# Hope_Badge.net
KiCad netlist of a schematic drawn in Altium Designer
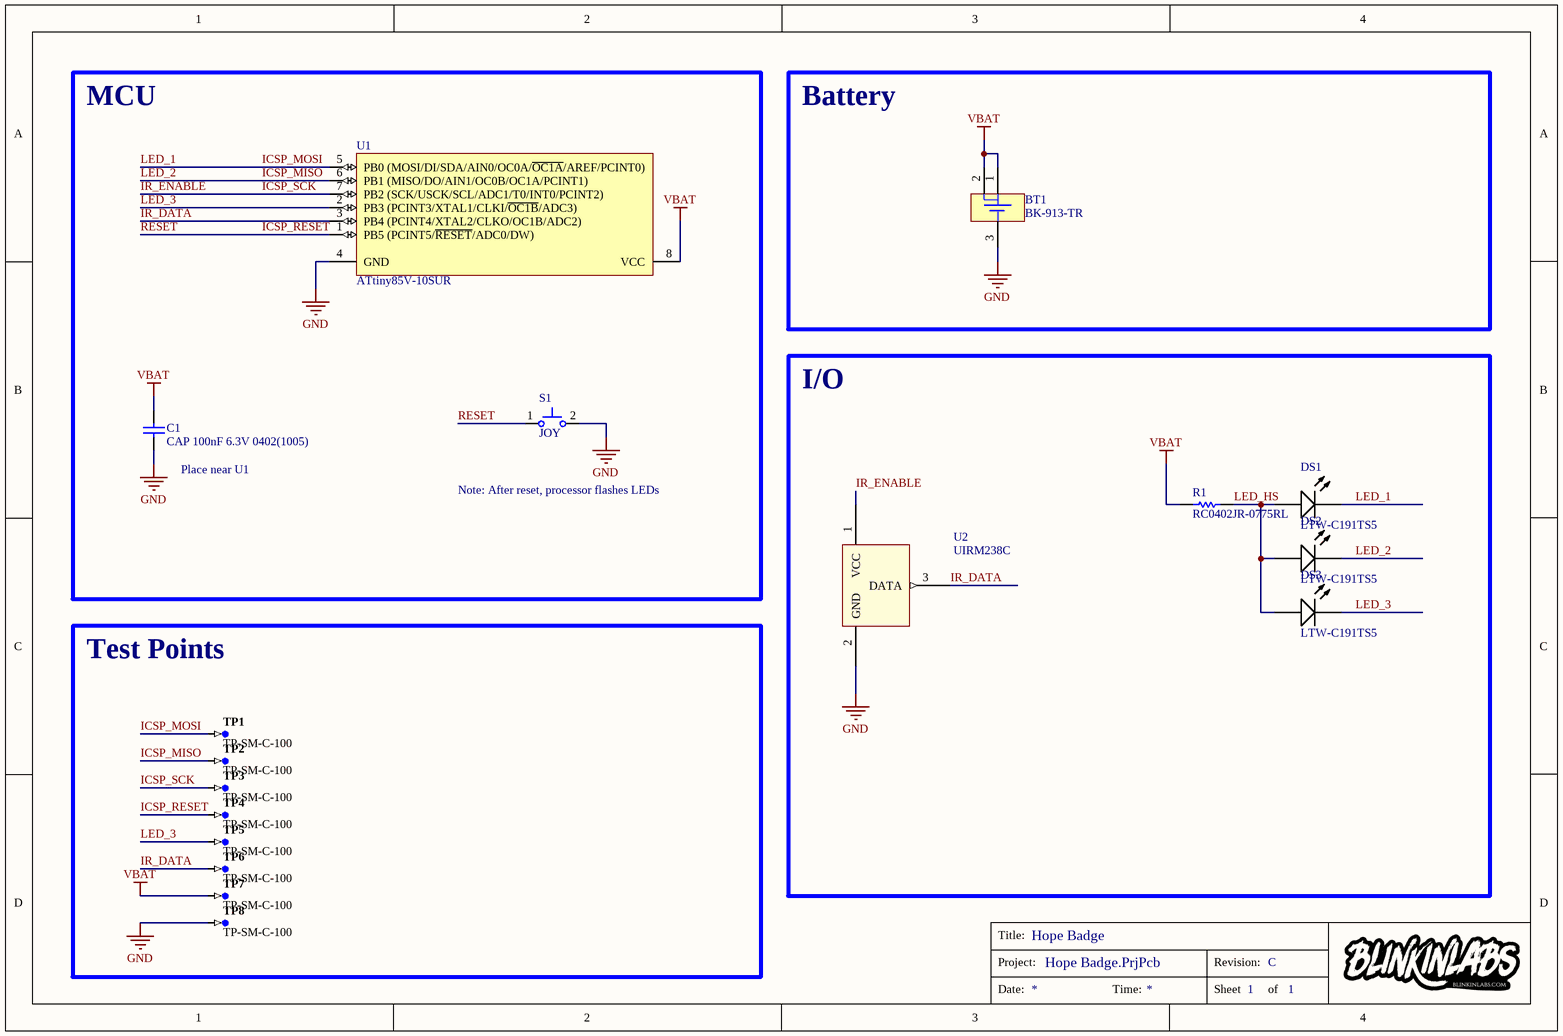
[diagram p0: Hope Badge.SchDoc]

(export (version "E")
  (design (tool "Eeschema 10.0.6"))
  (components
    (comp (ref "BT1")
      (value "BK-913-TR")
      (footprint "MPD-BK-913-3_V")
      (description "Battery Retainer for 20 mm Dia. Batteries, RoHS, Bag")
      (fields (field (name "MANUFACTURER") "Memory Protection Devices"))
      (libsource (lib "Altium Content Vault") (part "MPD-BK-913-TR-3"))
    )
    (comp (ref "C1")
      (value "CAP 100nF 6.3V 0402(1005)")
      (footprint "CAPC0402(1005)60_N")
      (description "CAP 100nF 6.3V -20% to +80% 0402 (1005 Metric) Thickness 0.6mm SMD")
      (fields (field (name "TOLERANCE") "-20% to +80%"))
      (libsource (lib "Altium Content Vault") (part "CMP-1034-02063-1"))
    )
    (comp (ref "DS1")
      (value "LTW-C191TS5")
      (footprint "LTST-LTW-C191TS5_V")
      (description "LED Uni-Color White, 70 mW, 20 mA, -20 to 80 degC, 2-Pin SMD, RoHS, Tape and Reel")
      (fields (field (name "TOLERANCE") "1%"))
      (libsource (lib "Altium Content Vault") (part "CMP-1674-00013-1"))
    )
    (comp (ref "DS2")
      (value "LTW-C191TS5")
      (footprint "LTST-LTW-C191TS5_V")
      (description "LED Uni-Color White, 70 mW, 20 mA, -20 to 80 degC, 2-Pin SMD, RoHS, Tape and Reel")
      (fields (field (name "TOLERANCE") "1%"))
      (libsource (lib "Altium Content Vault") (part "CMP-1674-00013-1"))
    )
    (comp (ref "DS3")
      (value "LTW-C191TS5")
      (footprint "LTST-LTW-C191TS5_V")
      (description "LED Uni-Color White, 70 mW, 20 mA, -20 to 80 degC, 2-Pin SMD, RoHS, Tape and Reel")
      (fields (field (name "TOLERANCE") "1%"))
      (libsource (lib "Altium Content Vault") (part "CMP-1674-00013-1"))
    )
    (comp (ref "R1")
      (value "RC0402JR-0775RL")
      (footprint "RESC1005X40X25ML5T10")
      (description "Chip Resistor, 75 Ohm, +/- 5%, 0.063 W, -55 to 155 degC, 0402 (1005 Metric), RoHS, Tape and Reel")
      (fields (field (name "TOLERANCE") "5%"))
      (libsource (lib "Altium Content Vault") (part "CMP-2002-08044-2"))
    )
    (comp (ref "S1")
      (value "JOY")
      (footprint "TS-1185")
      (description "Tact Switch, 3x4mm, no alignment pin, turtle style")
      (libsource (lib "Blinkinlabs") (part "TS-1185"))
    )
    (comp (ref "TP1")
      (value "TP-SM-C-100")
      (footprint "TP-SM-C-100")
      (description "Test Point, Surface Mount, Circular, Pad Diameter 1 mm")
      (fields (field (name "MANUFACTURER") "No Vendor"))
      (libsource (lib "Altium Content Vault") (part "TP-SM"))
    )
    (comp (ref "TP2")
      (value "TP-SM-C-100")
      (footprint "TP-SM-C-100")
      (description "Test Point, Surface Mount, Circular, Pad Diameter 1 mm")
      (fields (field (name "MANUFACTURER") "No Vendor"))
      (libsource (lib "Altium Content Vault") (part "CMP-0484-00002-2"))
    )
    (comp (ref "TP3")
      (value "TP-SM-C-100")
      (footprint "TP-SM-C-100")
      (description "Test Point, Surface Mount, Circular, Pad Diameter 1 mm")
      (fields (field (name "MANUFACTURER") "No Vendor"))
      (libsource (lib "Altium Content Vault") (part "CMP-0484-00002-2"))
    )
    (comp (ref "TP4")
      (value "TP-SM-C-100")
      (footprint "TP-SM-C-100")
      (description "Test Point, Surface Mount, Circular, Pad Diameter 1 mm")
      (fields (field (name "MANUFACTURER") "No Vendor"))
      (libsource (lib "Altium Content Vault") (part "CMP-0484-00002-2"))
    )
    (comp (ref "TP5")
      (value "TP-SM-C-100")
      (footprint "TP-SM-C-100")
      (description "Test Point, Surface Mount, Circular, Pad Diameter 1 mm")
      (fields (field (name "MANUFACTURER") "No Vendor"))
      (libsource (lib "Altium Content Vault") (part "CMP-0484-00002-2"))
    )
    (comp (ref "TP6")
      (value "TP-SM-C-100")
      (footprint "TP-SM-C-100")
      (description "Test Point, Surface Mount, Circular, Pad Diameter 1 mm")
      (fields (field (name "MANUFACTURER") "No Vendor"))
      (libsource (lib "Altium Content Vault") (part "CMP-0484-00002-2"))
    )
    (comp (ref "TP7")
      (value "TP-SM-C-100")
      (footprint "TP-SM-C-100")
      (description "Test Point, Surface Mount, Circular, Pad Diameter 1 mm")
      (fields (field (name "MANUFACTURER") "No Vendor"))
      (libsource (lib "Altium Content Vault") (part "CMP-0484-00002-2"))
    )
    (comp (ref "TP8")
      (value "TP-SM-C-100")
      (footprint "TP-SM-C-100")
      (description "Test Point, Surface Mount, Circular, Pad Diameter 1 mm")
      (fields (field (name "MANUFACTURER") "No Vendor"))
      (libsource (lib "Altium Content Vault") (part "CMP-0484-00002-2"))
    )
    (comp (ref "U1")
      (value "ATtiny85V-10SUR")
      (footprint "8S2_M")
      (libsource (lib "Altium Content Vault") (part "MC-8B-ATT25-IL8"))
    )
    (comp (ref "U2")
      (value "UIRM238C")
      (footprint "UIRM238C")
      (description "Infrared Receiver Module")
      (libsource (lib "Blinkinlabs") (part "UIRM238C"))
    )
  )
  (nets
    (net (code "1") (name "/ICSP_MISO") (class "Default")
      (node (ref "DS2") (pin "2") (pinfunction "K_2") (pintype "passive"))
      (node (ref "TP2") (pin "1") (pinfunction "1_1") (pintype "input"))
      (node (ref "U1") (pin "6") (pinfunction "PB1_(MISO/DO/AIN1/OC0B/OC1A/PCINT1)_6") (pintype "bidirectional"))
    )
    (net (code "2") (name "/ICSP_MOSI") (class "Default")
      (node (ref "DS1") (pin "2") (pinfunction "K_2") (pintype "passive"))
      (node (ref "TP1") (pin "1") (pinfunction "1_1") (pintype "input"))
      (node (ref "U1") (pin "5") (pinfunction "PB0_(MOSI/DI/SDA/AIN0/OC0A/~{OC1A}/AREF/PCINT0)_5") (pintype "bidirectional"))
    )
    (net (code "3") (name "/ICSP_RESET") (class "Default")
      (node (ref "S1") (pin "1") (pinfunction "1_1") (pintype "passive"))
      (node (ref "TP4") (pin "1") (pinfunction "1_1") (pintype "input"))
      (node (ref "U1") (pin "1") (pinfunction "PB5_(PCINT5/~{RESET}/ADC0/DW)_1") (pintype "bidirectional"))
    )
    (net (code "4") (name "/ICSP_SCK") (class "Default")
      (node (ref "TP3") (pin "1") (pinfunction "1_1") (pintype "input"))
      (node (ref "U1") (pin "7") (pinfunction "PB2_(SCK/USCK/SCL/ADC1/T0/INT0/PCINT2)_7") (pintype "bidirectional"))
      (node (ref "U2") (pin "1") (pinfunction "VCC_1") (pintype "power_in"))
    )
    (net (code "5") (name "/IR_DATA") (class "Default")
      (node (ref "TP6") (pin "1") (pinfunction "1_1") (pintype "input"))
      (node (ref "U1") (pin "3") (pinfunction "PB4_(PCINT4/XTAL2/CLKO/OC1B/ADC2)_3") (pintype "bidirectional"))
      (node (ref "U2") (pin "3") (pinfunction "DATA_3") (pintype "output"))
    )
    (net (code "6") (name "/LED_3") (class "Default")
      (node (ref "DS3") (pin "2") (pinfunction "K_2") (pintype "passive"))
      (node (ref "TP5") (pin "1") (pinfunction "1_1") (pintype "input"))
      (node (ref "U1") (pin "2") (pinfunction "PB3_(PCINT3/XTAL1/CLKI/~{OC1B}/ADC3)_2") (pintype "bidirectional"))
    )
    (net (code "7") (name "/LED_HS") (class "Default")
      (node (ref "DS1") (pin "1") (pinfunction "A_1") (pintype "passive"))
      (node (ref "DS2") (pin "1") (pinfunction "A_1") (pintype "passive"))
      (node (ref "DS3") (pin "1") (pinfunction "A_1") (pintype "passive"))
      (node (ref "R1") (pin "1") (pinfunction "1_1") (pintype "passive"))
    )
    (net (code "8") (name "GND") (class "Default")
      (node (ref "BT1") (pin "3") (pinfunction "NEGATIVE_3") (pintype "passive"))
      (node (ref "C1") (pin "1") (pinfunction "1_1") (pintype "passive"))
      (node (ref "S1") (pin "2") (pinfunction "2_2") (pintype "passive"))
      (node (ref "TP8") (pin "1") (pinfunction "1_1") (pintype "input"))
      (node (ref "U1") (pin "4") (pinfunction "GND_4") (pintype "power_in"))
      (node (ref "U2") (pin "2") (pinfunction "GND_2") (pintype "power_in"))
    )
    (net (code "9") (name "VBAT") (class "Default")
      (node (ref "BT1") (pin "1") (pinfunction "POSITIVE_1") (pintype "passive"))
      (node (ref "BT1") (pin "2") (pinfunction "POSITIVE_2") (pintype "passive"))
      (node (ref "C1") (pin "2") (pinfunction "2_2") (pintype "passive"))
      (node (ref "R1") (pin "2") (pinfunction "2_2") (pintype "passive"))
      (node (ref "TP7") (pin "1") (pinfunction "1_1") (pintype "input"))
      (node (ref "U1") (pin "8") (pinfunction "VCC_8") (pintype "power_in"))
    )
  )
)
